# PIN2DMD_Nucleo144.net
KiCad netlist of a schematic drawn in EAGLE
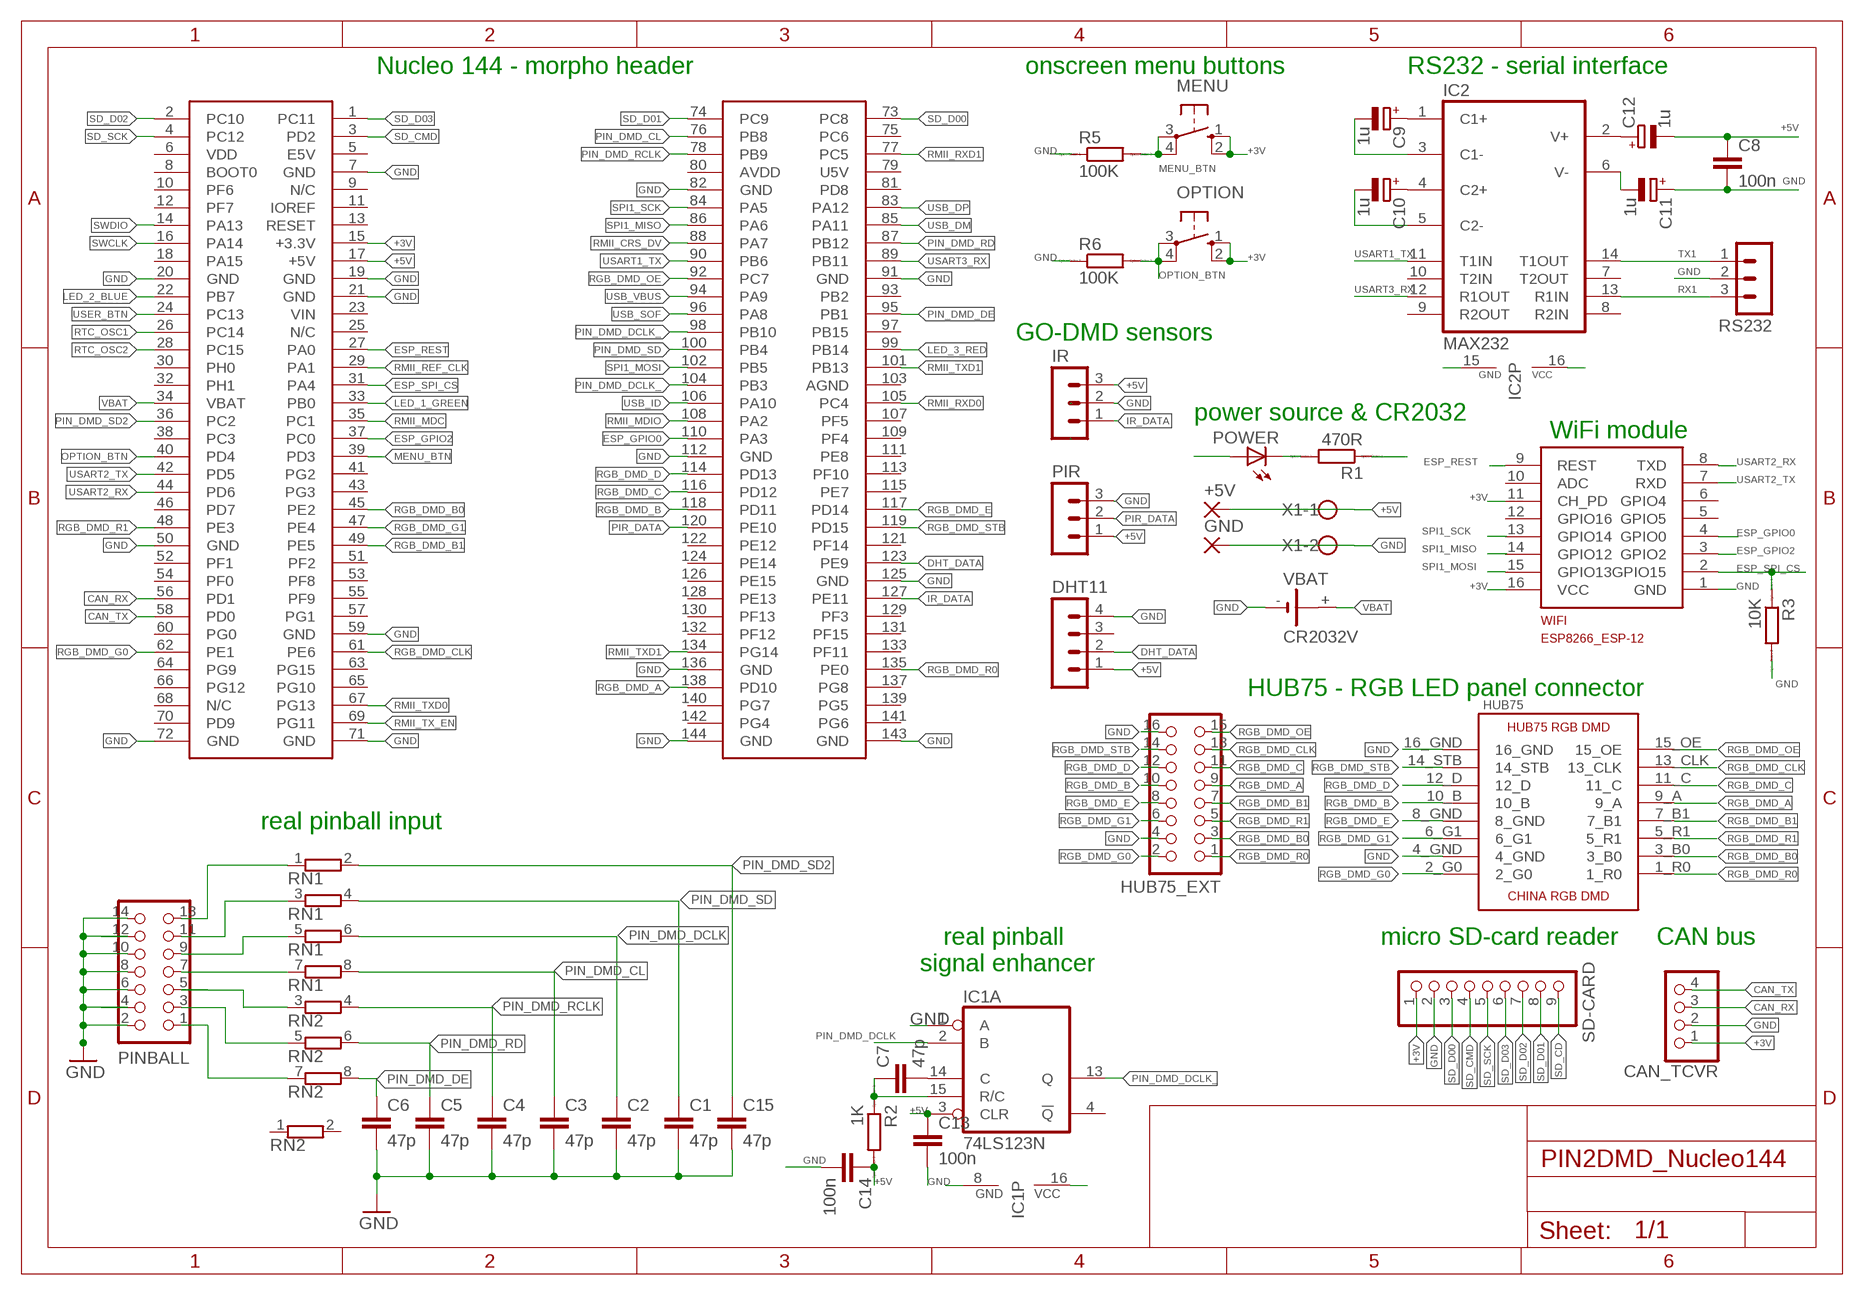
[diagram p0: schematic, sheet 1]

(export (version "E")
  (design (tool "Eeschema 10.0.6"))
  (components
    (comp (ref "+5V")
      (value "WIREPADSMD2,54-5,08")
      (footprint "eagle-import:SMD2,54-5,08")
      (libsource (lib "eagle-import") (part "WIREPADSMD2,54-5,08"))
    )
    (comp (ref "C1")
      (value "47p")
      (footprint "eagle-import:C025-024X044")
      (libsource (lib "eagle-import") (part "C-EU025-024X044"))
    )
    (comp (ref "C2")
      (value "47p")
      (footprint "eagle-import:C025-024X044")
      (libsource (lib "eagle-import") (part "C-EU025-024X044"))
    )
    (comp (ref "C3")
      (value "47p")
      (footprint "eagle-import:C025-024X044")
      (libsource (lib "eagle-import") (part "C-EU025-024X044"))
    )
    (comp (ref "C4")
      (value "47p")
      (footprint "eagle-import:C025-024X044")
      (libsource (lib "eagle-import") (part "C-EU025-024X044"))
    )
    (comp (ref "C5")
      (value "47p")
      (footprint "eagle-import:C025-024X044")
      (libsource (lib "eagle-import") (part "C-EU025-024X044"))
    )
    (comp (ref "C6")
      (value "47p")
      (footprint "eagle-import:C025-024X044")
      (libsource (lib "eagle-import") (part "C-EU025-024X044"))
    )
    (comp (ref "C7")
      (value "47p")
      (footprint "eagle-import:C025-024X044")
      (libsource (lib "eagle-import") (part "C-EU025-024X044"))
    )
    (comp (ref "C8")
      (value "100n")
      (footprint "eagle-import:C025-024X044")
      (libsource (lib "eagle-import") (part "C-EU025-024X044"))
    )
    (comp (ref "C9")
      (value "1u")
      (footprint "eagle-import:E2-4")
      (libsource (lib "eagle-import") (part "CPOL-EUE2-4"))
    )
    (comp (ref "C10")
      (value "1u")
      (footprint "eagle-import:E2-4")
      (libsource (lib "eagle-import") (part "CPOL-EUE2-4"))
    )
    (comp (ref "C11")
      (value "1u")
      (footprint "eagle-import:E2-4")
      (libsource (lib "eagle-import") (part "CPOL-EUE2-4"))
    )
    (comp (ref "C12")
      (value "1u")
      (footprint "eagle-import:E2-4")
      (libsource (lib "eagle-import") (part "CPOL-EUE2-4"))
    )
    (comp (ref "C13")
      (value "100n")
      (footprint "eagle-import:C025-024X044")
      (libsource (lib "eagle-import") (part "C-EU025-024X044"))
    )
    (comp (ref "C14")
      (value "100n")
      (footprint "eagle-import:C025-024X044")
      (libsource (lib "eagle-import") (part "C-EU025-024X044"))
    )
    (comp (ref "C15")
      (value "47p")
      (footprint "eagle-import:C025-024X044")
      (libsource (lib "eagle-import") (part "C-EU025-024X044"))
    )
    (comp (ref "CAN_TCVR")
      (value "PINHD-1X4")
      (footprint "eagle-import:1X04")
      (libsource (lib "eagle-import") (part "PINHD-1X4"))
    )
    (comp (ref "DHT11")
      (value "MA04-1")
      (footprint "eagle-import:MA04-1")
      (libsource (lib "eagle-import") (part "MA04-1"))
    )
    (comp (ref "GND")
      (value "WIREPADSMD2,54-5,08")
      (footprint "eagle-import:SMD2,54-5,08")
      (libsource (lib "eagle-import") (part "WIREPADSMD2,54-5,08"))
    )
    (comp (ref "HUB75")
      (value "RGB_DMD_HUB75_HEADER_FEMALE")
      (footprint "eagle-import:16_PIN_HUB75_RGB_FEMALE_DOWN")
      (libsource (lib "eagle-import") (part "RGB_DMD_HUB75_HEADER_FEMALE"))
    )
    (comp (ref "HUB75_EXT")
      (value "CON_HEADER_2X08B")
      (footprint "eagle-import:PINSHRD_PTH_2X08")
      (libsource (lib "eagle-import") (part "CON_HEADER_2X08B"))
    )
    (comp (ref "IC1")
      (value "74LS123N")
      (footprint "eagle-import:DIL16")
      (libsource (lib "eagle-import") (part "74123NLS"))
    )
    (comp (ref "IC2")
      (value "MAX232")
      (footprint "eagle-import:DIL16")
      (fields (field (name "MF") "MAXIM") (field (name "MPN") "MAX232ACPE+"))
      (libsource (lib "eagle-import") (part "MAX232"))
    )
    (comp (ref "IR")
      (value "MA03-1")
      (footprint "eagle-import:MA03-1")
      (libsource (lib "eagle-import") (part "MA03-1"))
    )
    (comp (ref "MENU")
      (value "10-XX")
      (footprint "eagle-import:B3F-10XX")
      (fields (field (name "MPN") "B3F-1000"))
      (libsource (lib "eagle-import") (part "10-XX"))
    )
    (comp (ref "OPTION")
      (value "10-XX")
      (footprint "eagle-import:B3F-10XX")
      (fields (field (name "MPN") "B3F-1000"))
      (libsource (lib "eagle-import") (part "10-XX"))
    )
    (comp (ref "PINBALL")
      (value "CON_HEADER_2X07-PTH-SHROUDED")
      (footprint "eagle-import:PINSHRD_PTH_2X07")
      (libsource (lib "eagle-import") (part "CON_HEADER_2X07-PTH-SHROUDED"))
    )
    (comp (ref "PIR")
      (value "MA03-1")
      (footprint "eagle-import:MA03-1")
      (libsource (lib "eagle-import") (part "MA03-1"))
    )
    (comp (ref "POWER")
      (value "LED3MM")
      (footprint "eagle-import:LED3MM")
      (libsource (lib "eagle-import") (part "LED3MM"))
    )
    (comp (ref "R1")
      (value "470R")
      (footprint "eagle-import:0207_10")
      (libsource (lib "eagle-import") (part "R0207/10"))
    )
    (comp (ref "R2")
      (value "1K")
      (footprint "eagle-import:0207_10")
      (libsource (lib "eagle-import") (part "R0207/10"))
    )
    (comp (ref "R3")
      (value "10K")
      (footprint "eagle-import:0207_10")
      (libsource (lib "eagle-import") (part "R0207/10"))
    )
    (comp (ref "R5")
      (value "100K")
      (footprint "eagle-import:0207_10")
      (libsource (lib "eagle-import") (part "R0207/10"))
    )
    (comp (ref "R6")
      (value "100K")
      (footprint "eagle-import:0207_10")
      (libsource (lib "eagle-import") (part "R0207/10"))
    )
    (comp (ref "RN1")
      (value "E4RP")
      (footprint "eagle-import:SIL8")
      (libsource (lib "eagle-import") (part "E4RP"))
    )
    (comp (ref "RN2")
      (value "E4RP")
      (footprint "eagle-import:SIL8")
      (libsource (lib "eagle-import") (part "E4RP"))
    )
    (comp (ref "RS232")
      (value "MA03-1")
      (footprint "eagle-import:MA03-1")
      (libsource (lib "eagle-import") (part "MA03-1"))
    )
    (comp (ref "SD-CARD")
      (value "PINHD-1X9")
      (footprint "eagle-import:1X09")
      (libsource (lib "eagle-import") (part "PINHD-1X9"))
    )
    (comp (ref "U$1")
      (value "NUCLEO-144")
      (footprint "eagle-import:NUCLEO-144")
      (libsource (lib "eagle-import") (part "NUCLEO-144"))
    )
    (comp (ref "VBAT")
      (value "CR2032V")
      (footprint "eagle-import:CR2032V")
      (libsource (lib "eagle-import") (part "CR2032V"))
    )
    (comp (ref "WIFI")
      (value "ESP8266_ESP-12")
      (footprint "eagle-import:ESP8266-ESP12")
      (libsource (lib "eagle-import") (part "ESP8266_ESP-12"))
    )
    (comp (ref "X1")
      (value "W237-102")
      (footprint "eagle-import:W237-102")
      (fields (field (name "MPN") "237-102"))
      (libsource (lib "eagle-import") (part "W237-102"))
    )
  )
  (nets
    (net (code "1") (name "+3V") (class "Default")
      (node (ref "CAN_TCVR") (pin "1") (pinfunction "1_1") (pintype "passive"))
      (node (ref "MENU") (pin "1") (pinfunction "S_1") (pintype "passive"))
      (node (ref "MENU") (pin "2") (pinfunction "S1_2") (pintype "passive"))
      (node (ref "OPTION") (pin "1") (pinfunction "S_1") (pintype "passive"))
      (node (ref "OPTION") (pin "2") (pinfunction "S1_2") (pintype "passive"))
      (node (ref "SD-CARD") (pin "1") (pinfunction "1_1") (pintype "passive"))
      (node (ref "U$1") (pin "15") (pinfunction "+3.3V_15") (pintype "bidirectional"))
      (node (ref "WIFI") (pin "11") (pinfunction "CH_PD_11") (pintype "bidirectional"))
      (node (ref "WIFI") (pin "16") (pinfunction "VCC_16") (pintype "bidirectional"))
    )
    (net (code "2") (name "+5V") (class "Default")
      (node (ref "+5V") (pin "1") (pinfunction "P_1") (pintype "passive"))
      (node (ref "C12") (pin "-") (pinfunction "-_-") (pintype "passive"))
      (node (ref "C13") (pin "1") (pinfunction "1_1") (pintype "passive"))
      (node (ref "C14") (pin "1") (pinfunction "1_1") (pintype "passive"))
      (node (ref "C8") (pin "1") (pinfunction "1_1") (pintype "passive"))
      (node (ref "DHT11") (pin "1") (pinfunction "1_1") (pintype "passive"))
      (node (ref "IC1") (pin "16") (pinfunction "VCC_16") (pintype "power_in"))
      (node (ref "IC1") (pin "3") (pinfunction "CLR_3") (pintype "input"))
      (node (ref "IC2") (pin "16") (pinfunction "VCC_16") (pintype "power_in"))
      (node (ref "IR") (pin "3") (pinfunction "3_3") (pintype "passive"))
      (node (ref "PIR") (pin "1") (pinfunction "1_1") (pintype "passive"))
      (node (ref "POWER") (pin "A") (pinfunction "A_A") (pintype "passive"))
      (node (ref "R2") (pin "2") (pinfunction "2_2") (pintype "passive"))
      (node (ref "U$1") (pin "17") (pinfunction "+5V_17") (pintype "bidirectional"))
      (node (ref "X1") (pin "1") (pinfunction "KL_1") (pintype "passive"))
    )
    (net (code "3") (name "/RX1") (class "Default")
      (node (ref "IC2") (pin "13") (pinfunction "R1IN_13") (pintype "input"))
      (node (ref "RS232") (pin "3") (pinfunction "3_3") (pintype "passive"))
    )
    (net (code "4") (name "/TX1") (class "Default")
      (node (ref "IC2") (pin "14") (pinfunction "T1OUT_14") (pintype "output"))
      (node (ref "RS232") (pin "1") (pinfunction "1_1") (pintype "passive"))
    )
    (net (code "5") (name "CAN_RX") (class "Default")
      (node (ref "CAN_TCVR") (pin "3") (pinfunction "3_3") (pintype "passive"))
      (node (ref "U$1") (pin "56") (pinfunction "PD1_56") (pintype "bidirectional"))
    )
    (net (code "6") (name "CAN_TX") (class "Default")
      (node (ref "CAN_TCVR") (pin "4") (pinfunction "4_4") (pintype "passive"))
      (node (ref "U$1") (pin "58") (pinfunction "PD0_58") (pintype "bidirectional"))
    )
    (net (code "7") (name "DHT_DATA") (class "Default")
      (node (ref "DHT11") (pin "2") (pinfunction "2_2") (pintype "passive"))
      (node (ref "U$1") (pin "123") (pinfunction "PE9_123") (pintype "bidirectional"))
    )
    (net (code "8") (name "ESP_GPIO0") (class "Default")
      (node (ref "U$1") (pin "110") (pinfunction "PA3_110") (pintype "bidirectional"))
      (node (ref "WIFI") (pin "4") (pinfunction "GPIO0_4") (pintype "bidirectional"))
    )
    (net (code "9") (name "ESP_GPIO2") (class "Default")
      (node (ref "U$1") (pin "37") (pinfunction "PC0_37") (pintype "bidirectional"))
      (node (ref "WIFI") (pin "3") (pinfunction "GPIO2_3") (pintype "bidirectional"))
    )
    (net (code "10") (name "ESP_REST") (class "Default")
      (node (ref "U$1") (pin "27") (pinfunction "PA0_27") (pintype "bidirectional"))
      (node (ref "WIFI") (pin "9") (pinfunction "REST_9") (pintype "bidirectional"))
    )
    (net (code "11") (name "ESP_SPI_CS") (class "Default")
      (node (ref "R3") (pin "1") (pinfunction "1_1") (pintype "passive"))
      (node (ref "U$1") (pin "31") (pinfunction "PA4_31") (pintype "bidirectional"))
      (node (ref "WIFI") (pin "2") (pinfunction "GPIO15_2") (pintype "bidirectional"))
    )
    (net (code "12") (name "GND") (class "Default")
      (node (ref "C1") (pin "2") (pinfunction "2_2") (pintype "passive"))
      (node (ref "C11") (pin "+") (pinfunction "+_+") (pintype "passive"))
      (node (ref "C13") (pin "2") (pinfunction "2_2") (pintype "passive"))
      (node (ref "C14") (pin "2") (pinfunction "2_2") (pintype "passive"))
      (node (ref "C15") (pin "2") (pinfunction "2_2") (pintype "passive"))
      (node (ref "C2") (pin "2") (pinfunction "2_2") (pintype "passive"))
      (node (ref "C3") (pin "2") (pinfunction "2_2") (pintype "passive"))
      (node (ref "C4") (pin "2") (pinfunction "2_2") (pintype "passive"))
      (node (ref "C5") (pin "2") (pinfunction "2_2") (pintype "passive"))
      (node (ref "C6") (pin "2") (pinfunction "2_2") (pintype "passive"))
      (node (ref "C8") (pin "2") (pinfunction "2_2") (pintype "passive"))
      (node (ref "CAN_TCVR") (pin "2") (pinfunction "2_2") (pintype "passive"))
      (node (ref "DHT11") (pin "4") (pinfunction "4_4") (pintype "passive"))
      (node (ref "GND") (pin "1") (pinfunction "P_1") (pintype "passive"))
      (node (ref "HUB75") (pin "16_GND") (pinfunction "16_GND_16_GND") (pintype "bidirectional"))
      (node (ref "HUB75") (pin "4_GND") (pinfunction "4_GND_4_GND") (pintype "bidirectional"))
      (node (ref "HUB75_EXT") (pin "16") (pinfunction "16_16") (pintype "passive"))
      (node (ref "HUB75_EXT") (pin "4") (pinfunction "4_4") (pintype "passive"))
      (node (ref "IC1") (pin "1") (pinfunction "A_1") (pintype "input"))
      (node (ref "IC1") (pin "8") (pinfunction "GND_8") (pintype "power_in"))
      (node (ref "IC2") (pin "15") (pinfunction "GND_15") (pintype "power_in"))
      (node (ref "IR") (pin "2") (pinfunction "2_2") (pintype "passive"))
      (node (ref "PINBALL") (pin "10") (pinfunction "10_10") (pintype "passive"))
      (node (ref "PINBALL") (pin "12") (pinfunction "12_12") (pintype "passive"))
      (node (ref "PINBALL") (pin "14") (pinfunction "14_14") (pintype "passive"))
      (node (ref "PINBALL") (pin "2") (pinfunction "2_2") (pintype "passive"))
      (node (ref "PINBALL") (pin "4") (pinfunction "4_4") (pintype "passive"))
      (node (ref "PINBALL") (pin "6") (pinfunction "6_6") (pintype "passive"))
      (node (ref "PINBALL") (pin "8") (pinfunction "8_8") (pintype "passive"))
      (node (ref "PIR") (pin "3") (pinfunction "3_3") (pintype "passive"))
      (node (ref "R1") (pin "1") (pinfunction "1_1") (pintype "passive"))
      (node (ref "R3") (pin "2") (pinfunction "2_2") (pintype "passive"))
      (node (ref "R5") (pin "1") (pinfunction "1_1") (pintype "passive"))
      (node (ref "R6") (pin "1") (pinfunction "1_1") (pintype "passive"))
      (node (ref "RS232") (pin "2") (pinfunction "2_2") (pintype "passive"))
      (node (ref "SD-CARD") (pin "2") (pinfunction "2_2") (pintype "passive"))
      (node (ref "U$1") (pin "112") (pinfunction "GND_112") (pintype "bidirectional"))
      (node (ref "U$1") (pin "125") (pinfunction "GND_125") (pintype "bidirectional"))
      (node (ref "U$1") (pin "136") (pinfunction "GND_136") (pintype "bidirectional"))
      (node (ref "U$1") (pin "143") (pinfunction "GND_143") (pintype "bidirectional"))
      (node (ref "U$1") (pin "144") (pinfunction "GND_144") (pintype "bidirectional"))
      (node (ref "U$1") (pin "19") (pinfunction "GND_19") (pintype "bidirectional"))
      (node (ref "U$1") (pin "20") (pinfunction "GND_20") (pintype "bidirectional"))
      (node (ref "U$1") (pin "21") (pinfunction "GND_21") (pintype "bidirectional"))
      (node (ref "U$1") (pin "50") (pinfunction "GND_50") (pintype "bidirectional"))
      (node (ref "U$1") (pin "59") (pinfunction "GND_59") (pintype "bidirectional"))
      (node (ref "U$1") (pin "7") (pinfunction "GND_7") (pintype "bidirectional"))
      (node (ref "U$1") (pin "71") (pinfunction "GND_71") (pintype "bidirectional"))
      (node (ref "U$1") (pin "72") (pinfunction "GND_72") (pintype "bidirectional"))
      (node (ref "U$1") (pin "82") (pinfunction "GND_82") (pintype "bidirectional"))
      (node (ref "U$1") (pin "91") (pinfunction "GND_91") (pintype "bidirectional"))
      (node (ref "VBAT") (pin "-") (pinfunction "-_-") (pintype "passive"))
      (node (ref "WIFI") (pin "1") (pinfunction "GND_1") (pintype "bidirectional"))
      (node (ref "X1") (pin "2") (pinfunction "KL_2") (pintype "passive"))
    )
    (net (code "13") (name "IR_DATA") (class "Default")
      (node (ref "IR") (pin "1") (pinfunction "1_1") (pintype "passive"))
      (node (ref "U$1") (pin "127") (pinfunction "PE11_127") (pintype "bidirectional"))
    )
    (net (code "14") (name "LED_1_GREEN") (class "Default")
      (node (ref "U$1") (pin "33") (pinfunction "PB0_33") (pintype "bidirectional"))
    )
    (net (code "15") (name "LED_2_BLUE") (class "Default")
      (node (ref "U$1") (pin "22") (pinfunction "PB7_22") (pintype "bidirectional"))
    )
    (net (code "16") (name "LED_3_RED") (class "Default")
      (node (ref "U$1") (pin "99") (pinfunction "PB14_99") (pintype "bidirectional"))
    )
    (net (code "17") (name "MENU_BTN") (class "Default")
      (node (ref "MENU") (pin "3") (pinfunction "P_3") (pintype "passive"))
      (node (ref "MENU") (pin "4") (pinfunction "P1_4") (pintype "passive"))
      (node (ref "R5") (pin "2") (pinfunction "2_2") (pintype "passive"))
      (node (ref "U$1") (pin "39") (pinfunction "PD3_39") (pintype "bidirectional"))
    )
    (net (code "18") (name "Net-(IC1A-C)") (class "Default")
      (node (ref "C7") (pin "2") (pinfunction "2_2") (pintype "passive"))
      (node (ref "IC1") (pin "14") (pinfunction "C_14") (pintype "input"))
    )
    (net (code "19") (name "Net-(IC1A-R{slash}C)") (class "Default")
      (node (ref "C7") (pin "1") (pinfunction "1_1") (pintype "passive"))
      (node (ref "IC1") (pin "15") (pinfunction "R/C_15") (pintype "input"))
      (node (ref "R2") (pin "1") (pinfunction "1_1") (pintype "passive"))
    )
    (net (code "20") (name "Net-(IC2A-C1+)") (class "Default")
      (node (ref "C9") (pin "+") (pinfunction "+_+") (pintype "passive"))
      (node (ref "IC2") (pin "1") (pinfunction "C1+_1") (pintype "bidirectional"))
    )
    (net (code "21") (name "Net-(IC2A-C1-)") (class "Default")
      (node (ref "C9") (pin "-") (pinfunction "-_-") (pintype "passive"))
      (node (ref "IC2") (pin "3") (pinfunction "C1-_3") (pintype "bidirectional"))
    )
    (net (code "22") (name "Net-(IC2A-C2+)") (class "Default")
      (node (ref "C10") (pin "+") (pinfunction "+_+") (pintype "passive"))
      (node (ref "IC2") (pin "4") (pinfunction "C2+_4") (pintype "bidirectional"))
    )
    (net (code "23") (name "Net-(IC2A-C2-)") (class "Default")
      (node (ref "C10") (pin "-") (pinfunction "-_-") (pintype "passive"))
      (node (ref "IC2") (pin "5") (pinfunction "C2-_5") (pintype "bidirectional"))
    )
    (net (code "24") (name "Net-(IC2A-V+)") (class "Default")
      (node (ref "C12") (pin "+") (pinfunction "+_+") (pintype "passive"))
      (node (ref "IC2") (pin "2") (pinfunction "V+_2") (pintype "bidirectional"))
    )
    (net (code "25") (name "Net-(IC2A-V-)") (class "Default")
      (node (ref "C11") (pin "-") (pinfunction "-_-") (pintype "passive"))
      (node (ref "IC2") (pin "6") (pinfunction "V-_6") (pintype "bidirectional"))
    )
    (net (code "26") (name "Net-(PINBALL-Pad13)") (class "Default")
      (node (ref "PINBALL") (pin "13") (pinfunction "13_13") (pintype "passive"))
      (node (ref "RN1") (pin "1") (pinfunction "1_1") (pintype "passive"))
    )
    (net (code "27") (name "Net-(POWER-C)") (class "Default")
      (node (ref "POWER") (pin "K") (pinfunction "C_K") (pintype "passive"))
      (node (ref "R1") (pin "2") (pinfunction "2_2") (pintype "passive"))
    )
    (net (code "28") (name "Net-(RN1B-1)") (class "Default")
      (node (ref "PINBALL") (pin "11") (pinfunction "11_11") (pintype "passive"))
      (node (ref "RN1") (pin "3") (pinfunction "1_3") (pintype "passive"))
    )
    (net (code "29") (name "Net-(RN1C-1)") (class "Default")
      (node (ref "PINBALL") (pin "9") (pinfunction "9_9") (pintype "passive"))
      (node (ref "RN1") (pin "5") (pinfunction "1_5") (pintype "passive"))
    )
    (net (code "30") (name "Net-(RN1D-1)") (class "Default")
      (node (ref "PINBALL") (pin "7") (pinfunction "7_7") (pintype "passive"))
      (node (ref "RN1") (pin "7") (pinfunction "1_7") (pintype "passive"))
    )
    (net (code "31") (name "Net-(RN2B-1)") (class "Default")
      (node (ref "PINBALL") (pin "5") (pinfunction "5_5") (pintype "passive"))
      (node (ref "RN2") (pin "3") (pinfunction "1_3") (pintype "passive"))
    )
    (net (code "32") (name "Net-(RN2C-1)") (class "Default")
      (node (ref "PINBALL") (pin "3") (pinfunction "3_3") (pintype "passive"))
      (node (ref "RN2") (pin "5") (pinfunction "1_5") (pintype "passive"))
    )
    (net (code "33") (name "Net-(RN2D-1)") (class "Default")
      (node (ref "PINBALL") (pin "1") (pinfunction "1_1") (pintype "passive"))
      (node (ref "RN2") (pin "7") (pinfunction "1_7") (pintype "passive"))
    )
    (net (code "34") (name "OPTION_BTN") (class "Default")
      (node (ref "OPTION") (pin "3") (pinfunction "P_3") (pintype "passive"))
      (node (ref "OPTION") (pin "4") (pinfunction "P1_4") (pintype "passive"))
      (node (ref "R6") (pin "2") (pinfunction "2_2") (pintype "passive"))
      (node (ref "U$1") (pin "40") (pinfunction "PD4_40") (pintype "bidirectional"))
    )
    (net (code "35") (name "PIN_DMD_CL") (class "Default")
      (node (ref "C3") (pin "1") (pinfunction "1_1") (pintype "passive"))
      (node (ref "RN1") (pin "8") (pinfunction "2_8") (pintype "passive"))
      (node (ref "U$1") (pin "76") (pinfunction "PB8_76") (pintype "bidirectional"))
    )
    (net (code "36") (name "PIN_DMD_DCLK") (class "Default")
      (node (ref "C2") (pin "1") (pinfunction "1_1") (pintype "passive"))
      (node (ref "IC1") (pin "2") (pinfunction "B_2") (pintype "input"))
      (node (ref "RN1") (pin "6") (pinfunction "2_6") (pintype "passive"))
    )
    (net (code "37") (name "PIN_DMD_DCLK_") (class "Default")
      (node (ref "IC1") (pin "13") (pinfunction "Q_13") (pintype "output"))
      (node (ref "U$1") (pin "104") (pinfunction "PB3_104") (pintype "bidirectional"))
      (node (ref "U$1") (pin "98") (pinfunction "PB10_98") (pintype "bidirectional"))
    )
    (net (code "38") (name "PIN_DMD_DE") (class "Default")
      (node (ref "C6") (pin "1") (pinfunction "1_1") (pintype "passive"))
      (node (ref "RN2") (pin "8") (pinfunction "2_8") (pintype "passive"))
      (node (ref "U$1") (pin "95") (pinfunction "PB1_95") (pintype "bidirectional"))
    )
    (net (code "39") (name "PIN_DMD_RCLK") (class "Default")
      (node (ref "C4") (pin "1") (pinfunction "1_1") (pintype "passive"))
      (node (ref "RN2") (pin "4") (pinfunction "2_4") (pintype "passive"))
      (node (ref "U$1") (pin "78") (pinfunction "PB9_78") (pintype "bidirectional"))
    )
    (net (code "40") (name "PIN_DMD_RD") (class "Default")
      (node (ref "C5") (pin "1") (pinfunction "1_1") (pintype "passive"))
      (node (ref "RN2") (pin "6") (pinfunction "2_6") (pintype "passive"))
      (node (ref "U$1") (pin "87") (pinfunction "PB12_87") (pintype "bidirectional"))
    )
    (net (code "41") (name "PIN_DMD_SD") (class "Default")
      (node (ref "C1") (pin "1") (pinfunction "1_1") (pintype "passive"))
      (node (ref "RN1") (pin "4") (pinfunction "2_4") (pintype "passive"))
      (node (ref "U$1") (pin "100") (pinfunction "PB4_100") (pintype "bidirectional"))
    )
    (net (code "42") (name "PIN_DMD_SD2") (class "Default")
      (node (ref "C15") (pin "1") (pinfunction "1_1") (pintype "passive"))
      (node (ref "RN1") (pin "2") (pinfunction "2_2") (pintype "passive"))
      (node (ref "U$1") (pin "36") (pinfunction "PC2_36") (pintype "bidirectional"))
    )
    (net (code "43") (name "PIR_DATA") (class "Default")
      (node (ref "PIR") (pin "2") (pinfunction "2_2") (pintype "passive"))
      (node (ref "U$1") (pin "120") (pinfunction "PE10_120") (pintype "bidirectional"))
    )
    (net (code "44") (name "RGB_DMD_A") (class "Default")
      (node (ref "HUB75") (pin "9_A") (pinfunction "9_A_9_A") (pintype "bidirectional"))
      (node (ref "HUB75_EXT") (pin "9") (pinfunction "9_9") (pintype "passive"))
      (node (ref "U$1") (pin "138") (pinfunction "PD10_138") (pintype "bidirectional"))
    )
    (net (code "45") (name "RGB_DMD_B") (class "Default")
      (node (ref "HUB75") (pin "10_B") (pinfunction "10_B_10_B") (pintype "bidirectional"))
      (node (ref "HUB75_EXT") (pin "10") (pinfunction "10_10") (pintype "passive"))
      (node (ref "U$1") (pin "118") (pinfunction "PD11_118") (pintype "bidirectional"))
    )
    (net (code "46") (name "RGB_DMD_B0") (class "Default")
      (node (ref "HUB75") (pin "3_B0") (pinfunction "3_B0_3_B0") (pintype "bidirectional"))
      (node (ref "HUB75_EXT") (pin "3") (pinfunction "3_3") (pintype "passive"))
      (node (ref "U$1") (pin "45") (pinfunction "PE2_45") (pintype "bidirectional"))
    )
    (net (code "47") (name "RGB_DMD_B1") (class "Default")
      (node (ref "HUB75") (pin "7_B1") (pinfunction "7_B1_7_B1") (pintype "bidirectional"))
      (node (ref "HUB75_EXT") (pin "7") (pinfunction "7_7") (pintype "passive"))
      (node (ref "U$1") (pin "49") (pinfunction "PE5_49") (pintype "bidirectional"))
    )
    (net (code "48") (name "RGB_DMD_C") (class "Default")
      (node (ref "HUB75") (pin "11_C") (pinfunction "11_C_11_C") (pintype "bidirectional"))
      (node (ref "HUB75_EXT") (pin "11") (pinfunction "11_11") (pintype "passive"))
      (node (ref "U$1") (pin "116") (pinfunction "PD12_116") (pintype "bidirectional"))
    )
    (net (code "49") (name "RGB_DMD_CLK") (class "Default")
      (node (ref "HUB75") (pin "13_CLK") (pinfunction "13_CLK_13_CLK") (pintype "bidirectional"))
      (node (ref "HUB75_EXT") (pin "13") (pinfunction "13_13") (pintype "passive"))
      (node (ref "U$1") (pin "61") (pinfunction "PE6_61") (pintype "bidirectional"))
    )
    (net (code "50") (name "RGB_DMD_D") (class "Default")
      (node (ref "HUB75") (pin "12_D") (pinfunction "12_D_12_D") (pintype "bidirectional"))
      (node (ref "HUB75_EXT") (pin "12") (pinfunction "12_12") (pintype "passive"))
      (node (ref "U$1") (pin "114") (pinfunction "PD13_114") (pintype "bidirectional"))
    )
    (net (code "51") (name "RGB_DMD_E") (class "Default")
      (node (ref "HUB75") (pin "8_GND") (pinfunction "8_GND_8_GND") (pintype "bidirectional"))
      (node (ref "HUB75_EXT") (pin "8") (pinfunction "8_8") (pintype "passive"))
      (node (ref "U$1") (pin "117") (pinfunction "PD14_117") (pintype "bidirectional"))
    )
    (net (code "52") (name "RGB_DMD_G0") (class "Default")
      (node (ref "HUB75") (pin "2_G0") (pinfunction "2_G0_2_G0") (pintype "bidirectional"))
      (node (ref "HUB75_EXT") (pin "2") (pinfunction "2_2") (pintype "passive"))
      (node (ref "U$1") (pin "62") (pinfunction "PE1_62") (pintype "bidirectional"))
    )
    (net (code "53") (name "RGB_DMD_G1") (class "Default")
      (node (ref "HUB75") (pin "6_G1") (pinfunction "6_G1_6_G1") (pintype "bidirectional"))
      (node (ref "HUB75_EXT") (pin "6") (pinfunction "6_6") (pintype "passive"))
      (node (ref "U$1") (pin "47") (pinfunction "PE4_47") (pintype "bidirectional"))
    )
    (net (code "54") (name "RGB_DMD_OE") (class "Default")
      (node (ref "HUB75") (pin "15_OE") (pinfunction "15_OE_15_OE") (pintype "bidirectional"))
      (node (ref "HUB75_EXT") (pin "15") (pinfunction "15_15") (pintype "passive"))
      (node (ref "U$1") (pin "92") (pinfunction "PC7_92") (pintype "bidirectional"))
    )
    (net (code "55") (name "RGB_DMD_R0") (class "Default")
      (node (ref "HUB75") (pin "1_R0") (pinfunction "1_R0_1_R0") (pintype "bidirectional"))
      (node (ref "HUB75_EXT") (pin "1") (pinfunction "1_1") (pintype "passive"))
      (node (ref "U$1") (pin "135") (pinfunction "PE0_135") (pintype "bidirectional"))
    )
    (net (code "56") (name "RGB_DMD_R1") (class "Default")
      (node (ref "HUB75") (pin "5_R1") (pinfunction "5_R1_5_R1") (pintype "bidirectional"))
      (node (ref "HUB75_EXT") (pin "5") (pinfunction "5_5") (pintype "passive"))
      (node (ref "U$1") (pin "48") (pinfunction "PE3_48") (pintype "bidirectional"))
    )
    (net (code "57") (name "RGB_DMD_STB") (class "Default")
      (node (ref "HUB75") (pin "14_STB") (pinfunction "14_STB_14_STB") (pintype "bidirectional"))
      (node (ref "HUB75_EXT") (pin "14") (pinfunction "14_14") (pintype "passive"))
      (node (ref "U$1") (pin "119") (pinfunction "PD15_119") (pintype "bidirectional"))
    )
    (net (code "58") (name "RMII_CRS_DV") (class "Default")
      (node (ref "U$1") (pin "88") (pinfunction "PA7_88") (pintype "bidirectional"))
    )
    (net (code "59") (name "RMII_MDC") (class "Default")
      (node (ref "U$1") (pin "35") (pinfunction "PC1_35") (pintype "bidirectional"))
    )
    (net (code "60") (name "RMII_MDIO") (class "Default")
      (node (ref "U$1") (pin "108") (pinfunction "PA2_108") (pintype "bidirectional"))
    )
    (net (code "61") (name "RMII_REF_CLK") (class "Default")
      (node (ref "U$1") (pin "29") (pinfunction "PA1_29") (pintype "bidirectional"))
    )
    (net (code "62") (name "RMII_RXD0") (class "Default")
      (node (ref "U$1") (pin "105") (pinfunction "PC4_105") (pintype "bidirectional"))
    )
    (net (code "63") (name "RMII_RXD1") (class "Default")
      (node (ref "U$1") (pin "77") (pinfunction "PC5_77") (pintype "bidirectional"))
    )
    (net (code "64") (name "RMII_TXD0") (class "Default")
      (node (ref "U$1") (pin "67") (pinfunction "PG13_67") (pintype "bidirectional"))
    )
    (net (code "65") (name "RMII_TXD1") (class "Default")
      (node (ref "U$1") (pin "101") (pinfunction "PB13_101") (pintype "bidirectional"))
      (node (ref "U$1") (pin "134") (pinfunction "PG14_134") (pintype "bidirectional"))
    )
    (net (code "66") (name "RMII_TX_EN") (class "Default")
      (node (ref "U$1") (pin "69") (pinfunction "PG11_69") (pintype "bidirectional"))
    )
    (net (code "67") (name "RTC_OSC1") (class "Default")
      (node (ref "U$1") (pin "26") (pinfunction "PC14_26") (pintype "bidirectional"))
    )
    (net (code "68") (name "RTC_OSC2") (class "Default")
      (node (ref "U$1") (pin "28") (pinfunction "PC15_28") (pintype "bidirectional"))
    )
    (net (code "69") (name "SD_CD") (class "Default")
      (node (ref "SD-CARD") (pin "9") (pinfunction "9_9") (pintype "passive"))
    )
    (net (code "70") (name "SD_CMD") (class "Default")
      (node (ref "SD-CARD") (pin "4") (pinfunction "4_4") (pintype "passive"))
      (node (ref "U$1") (pin "3") (pinfunction "PD2_3") (pintype "bidirectional"))
    )
    (net (code "71") (name "SD_D00") (class "Default")
      (node (ref "SD-CARD") (pin "3") (pinfunction "3_3") (pintype "passive"))
      (node (ref "U$1") (pin "73") (pinfunction "PC8_73") (pintype "bidirectional"))
    )
    (net (code "72") (name "SD_D01") (class "Default")
      (node (ref "SD-CARD") (pin "8") (pinfunction "8_8") (pintype "passive"))
      (node (ref "U$1") (pin "74") (pinfunction "PC9_74") (pintype "bidirectional"))
    )
    (net (code "73") (name "SD_D02") (class "Default")
      (node (ref "SD-CARD") (pin "7") (pinfunction "7_7") (pintype "passive"))
      (node (ref "U$1") (pin "2") (pinfunction "PC10_2") (pintype "bidirectional"))
    )
    (net (code "74") (name "SD_D03") (class "Default")
      (node (ref "SD-CARD") (pin "6") (pinfunction "6_6") (pintype "passive"))
      (node (ref "U$1") (pin "1") (pinfunction "PC11_1") (pintype "bidirectional"))
    )
    (net (code "75") (name "SD_SCK") (class "Default")
      (node (ref "SD-CARD") (pin "5") (pinfunction "5_5") (pintype "passive"))
      (node (ref "U$1") (pin "4") (pinfunction "PC12_4") (pintype "bidirectional"))
    )
    (net (code "76") (name "SPI1_MISO") (class "Default")
      (node (ref "U$1") (pin "86") (pinfunction "PA6_86") (pintype "bidirectional"))
      (node (ref "WIFI") (pin "14") (pinfunction "GPIO12_14") (pintype "bidirectional"))
    )
    (net (code "77") (name "SPI1_MOSI") (class "Default")
      (node (ref "U$1") (pin "102") (pinfunction "PB5_102") (pintype "bidirectional"))
      (node (ref "WIFI") (pin "15") (pinfunction "GPIO13_15") (pintype "bidirectional"))
    )
    (net (code "78") (name "SPI1_SCK") (class "Default")
      (node (ref "U$1") (pin "84") (pinfunction "PA5_84") (pintype "bidirectional"))
      (node (ref "WIFI") (pin "13") (pinfunction "GPIO14_13") (pintype "bidirectional"))
    )
    (net (code "79") (name "SWCLK") (class "Default")
      (node (ref "U$1") (pin "16") (pinfunction "PA14_16") (pintype "bidirectional"))
    )
    (net (code "80") (name "SWDIO") (class "Default")
      (node (ref "U$1") (pin "14") (pinfunction "PA13_14") (pintype "bidirectional"))
    )
    (net (code "81") (name "USART1_TX") (class "Default")
      (node (ref "IC2") (pin "11") (pinfunction "T1IN_11") (pintype "input"))
      (node (ref "U$1") (pin "90") (pinfunction "PB6_90") (pintype "bidirectional"))
    )
    (net (code "82") (name "USART2_RX") (class "Default")
      (node (ref "U$1") (pin "44") (pinfunction "PD6_44") (pintype "bidirectional"))
      (node (ref "WIFI") (pin "8") (pinfunction "TXD_8") (pintype "bidirectional"))
    )
    (net (code "83") (name "USART2_TX") (class "Default")
      (node (ref "U$1") (pin "42") (pinfunction "PD5_42") (pintype "bidirectional"))
      (node (ref "WIFI") (pin "7") (pinfunction "RXD_7") (pintype "bidirectional"))
    )
    (net (code "84") (name "USART3_RX") (class "Default")
      (node (ref "IC2") (pin "12") (pinfunction "R1OUT_12") (pintype "output"))
      (node (ref "U$1") (pin "89") (pinfunction "PB11_89") (pintype "bidirectional"))
    )
    (net (code "85") (name "USB_DM") (class "Default")
      (node (ref "U$1") (pin "85") (pinfunction "PA11_85") (pintype "bidirectional"))
    )
    (net (code "86") (name "USB_DP") (class "Default")
      (node (ref "U$1") (pin "83") (pinfunction "PA12_83") (pintype "bidirectional"))
    )
    (net (code "87") (name "USB_ID") (class "Default")
      (node (ref "U$1") (pin "106") (pinfunction "PA10_106") (pintype "bidirectional"))
    )
    (net (code "88") (name "USB_SOF") (class "Default")
      (node (ref "U$1") (pin "96") (pinfunction "PA8_96") (pintype "bidirectional"))
    )
    (net (code "89") (name "USB_VBUS") (class "Default")
      (node (ref "U$1") (pin "94") (pinfunction "PA9_94") (pintype "bidirectional"))
    )
    (net (code "90") (name "USER_BTN") (class "Default")
      (node (ref "U$1") (pin "24") (pinfunction "PC13_24") (pintype "bidirectional"))
    )
    (net (code "91") (name "VBAT") (class "Default")
      (node (ref "U$1") (pin "34") (pinfunction "VBAT_34") (pintype "bidirectional"))
      (node (ref "VBAT") (pin "+") (pinfunction "+_+") (pintype "passive"))
    )
    (net (code "92") (name "unconnected-(DHT11-Pad3)") (class "Default")
      (node (ref "DHT11") (pin "3") (pinfunction "3_3") (pintype "passive"))
    )
    (net (code "93") (name "unconnected-(IC1A-~{Q}-Pad4)") (class "Default")
      (node (ref "IC1") (pin "4") (pinfunction "~{Q}_4") (pintype "output"))
    )
    (net (code "94") (name "unconnected-(IC2A-R2IN-Pad8)") (class "Default")
      (node (ref "IC2") (pin "8") (pinfunction "R2IN_8") (pintype "input"))
    )
    (net (code "95") (name "unconnected-(IC2A-R2OUT-Pad9)") (class "Default")
      (node (ref "IC2") (pin "9") (pinfunction "R2OUT_9") (pintype "output"))
    )
    (net (code "96") (name "unconnected-(IC2A-T2IN-Pad10)") (class "Default")
      (node (ref "IC2") (pin "10") (pinfunction "T2IN_10") (pintype "input"))
    )
    (net (code "97") (name "unconnected-(IC2A-T2OUT-Pad7)") (class "Default")
      (node (ref "IC2") (pin "7") (pinfunction "T2OUT_7") (pintype "output"))
    )
    (net (code "98") (name "unconnected-(RN2-Pad1)") (class "Default")
      (node (ref "RN2") (pin "1") (pinfunction "1_1") (pintype "passive"))
    )
    (net (code "99") (name "unconnected-(RN2-Pad2)") (class "Default")
      (node (ref "RN2") (pin "2") (pinfunction "2_2") (pintype "passive"))
    )
    (net (code "100") (name "unconnected-(U$1-AGND-Pad103)") (class "Default")
      (node (ref "U$1") (pin "103") (pinfunction "AGND_103") (pintype "bidirectional"))
    )
    (net (code "101") (name "unconnected-(U$1-AVDD-Pad80)") (class "Default")
      (node (ref "U$1") (pin "80") (pinfunction "AVDD_80") (pintype "bidirectional"))
    )
    (net (code "102") (name "unconnected-(U$1-BOOT0-Pad8)") (class "Default")
      (node (ref "U$1") (pin "8") (pinfunction "BOOT0_8") (pintype "bidirectional"))
    )
    (net (code "103") (name "unconnected-(U$1-E5V-Pad5)") (class "Default")
      (node (ref "U$1") (pin "5") (pinfunction "E5V_5") (pintype "bidirectional"))
    )
    (net (code "104") (name "unconnected-(U$1-IOREF-Pad11)") (class "Default")
      (node (ref "U$1") (pin "11") (pinfunction "IOREF_11") (pintype "bidirectional"))
    )
    (net (code "105") (name "unconnected-(U$1-N{slash}C-Pad9)") (class "Default")
      (node (ref "U$1") (pin "9") (pinfunction "N/C_9") (pintype "bidirectional"))
    )
    (net (code "106") (name "unconnected-(U$1-N{slash}C-Pad25)") (class "Default")
      (node (ref "U$1") (pin "25") (pinfunction "N/C_25") (pintype "bidirectional"))
    )
    (net (code "107") (name "unconnected-(U$1-N{slash}C-Pad68)") (class "Default")
      (node (ref "U$1") (pin "68") (pinfunction "N/C_68") (pintype "bidirectional"))
    )
    (net (code "108") (name "unconnected-(U$1-PA15-Pad18)") (class "Default")
      (node (ref "U$1") (pin "18") (pinfunction "PA15_18") (pintype "bidirectional"))
    )
    (net (code "109") (name "unconnected-(U$1-PB2-Pad93)") (class "Default")
      (node (ref "U$1") (pin "93") (pinfunction "PB2_93") (pintype "bidirectional"))
    )
    (net (code "110") (name "unconnected-(U$1-PB15-Pad97)") (class "Default")
      (node (ref "U$1") (pin "97") (pinfunction "PB15_97") (pintype "bidirectional"))
    )
    (net (code "111") (name "unconnected-(U$1-PC3-Pad38)") (class "Default")
      (node (ref "U$1") (pin "38") (pinfunction "PC3_38") (pintype "bidirectional"))
    )
    (net (code "112") (name "unconnected-(U$1-PC6-Pad75)") (class "Default")
      (node (ref "U$1") (pin "75") (pinfunction "PC6_75") (pintype "bidirectional"))
    )
    (net (code "113") (name "unconnected-(U$1-PD7-Pad46)") (class "Default")
      (node (ref "U$1") (pin "46") (pinfunction "PD7_46") (pintype "bidirectional"))
    )
    (net (code "114") (name "unconnected-(U$1-PD8-Pad81)") (class "Default")
      (node (ref "U$1") (pin "81") (pinfunction "PD8_81") (pintype "bidirectional"))
    )
    (net (code "115") (name "unconnected-(U$1-PD9-Pad70)") (class "Default")
      (node (ref "U$1") (pin "70") (pinfunction "PD9_70") (pintype "bidirectional"))
    )
    (net (code "116") (name "unconnected-(U$1-PE7-Pad115)") (class "Default")
      (node (ref "U$1") (pin "115") (pinfunction "PE7_115") (pintype "bidirectional"))
    )
    (net (code "117") (name "unconnected-(U$1-PE8-Pad111)") (class "Default")
      (node (ref "U$1") (pin "111") (pinfunction "PE8_111") (pintype "bidirectional"))
    )
    (net (code "118") (name "unconnected-(U$1-PE12-Pad122)") (class "Default")
      (node (ref "U$1") (pin "122") (pinfunction "PE12_122") (pintype "bidirectional"))
    )
    (net (code "119") (name "unconnected-(U$1-PE13-Pad128)") (class "Default")
      (node (ref "U$1") (pin "128") (pinfunction "PE13_128") (pintype "bidirectional"))
    )
    (net (code "120") (name "unconnected-(U$1-PE14-Pad124)") (class "Default")
      (node (ref "U$1") (pin "124") (pinfunction "PE14_124") (pintype "bidirectional"))
    )
    (net (code "121") (name "unconnected-(U$1-PE15-Pad126)") (class "Default")
      (node (ref "U$1") (pin "126") (pinfunction "PE15_126") (pintype "bidirectional"))
    )
    (net (code "122") (name "unconnected-(U$1-PF0-Pad54)") (class "Default")
      (node (ref "U$1") (pin "54") (pinfunction "PF0_54") (pintype "bidirectional"))
    )
    (net (code "123") (name "unconnected-(U$1-PF1-Pad52)") (class "Default")
      (node (ref "U$1") (pin "52") (pinfunction "PF1_52") (pintype "bidirectional"))
    )
    (net (code "124") (name "unconnected-(U$1-PF2-Pad51)") (class "Default")
      (node (ref "U$1") (pin "51") (pinfunction "PF2_51") (pintype "bidirectional"))
    )
    (net (code "125") (name "unconnected-(U$1-PF3-Pad129)") (class "Default")
      (node (ref "U$1") (pin "129") (pinfunction "PF3_129") (pintype "bidirectional"))
    )
    (net (code "126") (name "unconnected-(U$1-PF4-Pad109)") (class "Default")
      (node (ref "U$1") (pin "109") (pinfunction "PF4_109") (pintype "bidirectional"))
    )
    (net (code "127") (name "unconnected-(U$1-PF5-Pad107)") (class "Default")
      (node (ref "U$1") (pin "107") (pinfunction "PF5_107") (pintype "bidirectional"))
    )
    (net (code "128") (name "unconnected-(U$1-PF6-Pad10)") (class "Default")
      (node (ref "U$1") (pin "10") (pinfunction "PF6_10") (pintype "bidirectional"))
    )
    (net (code "129") (name "unconnected-(U$1-PF7-Pad12)") (class "Default")
      (node (ref "U$1") (pin "12") (pinfunction "PF7_12") (pintype "bidirectional"))
    )
    (net (code "130") (name "unconnected-(U$1-PF8-Pad53)") (class "Default")
      (node (ref "U$1") (pin "53") (pinfunction "PF8_53") (pintype "bidirectional"))
    )
    (net (code "131") (name "unconnected-(U$1-PF9-Pad55)") (class "Default")
      (node (ref "U$1") (pin "55") (pinfunction "PF9_55") (pintype "bidirectional"))
    )
    (net (code "132") (name "unconnected-(U$1-PF10-Pad113)") (class "Default")
      (node (ref "U$1") (pin "113") (pinfunction "PF10_113") (pintype "bidirectional"))
    )
    (net (code "133") (name "unconnected-(U$1-PF11-Pad133)") (class "Default")
      (node (ref "U$1") (pin "133") (pinfunction "PF11_133") (pintype "bidirectional"))
    )
    (net (code "134") (name "unconnected-(U$1-PF12-Pad132)") (class "Default")
      (node (ref "U$1") (pin "132") (pinfunction "PF12_132") (pintype "bidirectional"))
    )
    (net (code "135") (name "unconnected-(U$1-PF13-Pad130)") (class "Default")
      (node (ref "U$1") (pin "130") (pinfunction "PF13_130") (pintype "bidirectional"))
    )
    (net (code "136") (name "unconnected-(U$1-PF14-Pad121)") (class "Default")
      (node (ref "U$1") (pin "121") (pinfunction "PF14_121") (pintype "bidirectional"))
    )
    (net (code "137") (name "unconnected-(U$1-PF15-Pad131)") (class "Default")
      (node (ref "U$1") (pin "131") (pinfunction "PF15_131") (pintype "bidirectional"))
    )
    (net (code "138") (name "unconnected-(U$1-PG0-Pad60)") (class "Default")
      (node (ref "U$1") (pin "60") (pinfunction "PG0_60") (pintype "bidirectional"))
    )
    (net (code "139") (name "unconnected-(U$1-PG1-Pad57)") (class "Default")
      (node (ref "U$1") (pin "57") (pinfunction "PG1_57") (pintype "bidirectional"))
    )
    (net (code "140") (name "unconnected-(U$1-PG2-Pad41)") (class "Default")
      (node (ref "U$1") (pin "41") (pinfunction "PG2_41") (pintype "bidirectional"))
    )
    (net (code "141") (name "unconnected-(U$1-PG3-Pad43)") (class "Default")
      (node (ref "U$1") (pin "43") (pinfunction "PG3_43") (pintype "bidirectional"))
    )
    (net (code "142") (name "unconnected-(U$1-PG4-Pad142)") (class "Default")
      (node (ref "U$1") (pin "142") (pinfunction "PG4_142") (pintype "bidirectional"))
    )
    (net (code "143") (name "unconnected-(U$1-PG5-Pad139)") (class "Default")
      (node (ref "U$1") (pin "139") (pinfunction "PG5_139") (pintype "bidirectional"))
    )
    (net (code "144") (name "unconnected-(U$1-PG6-Pad141)") (class "Default")
      (node (ref "U$1") (pin "141") (pinfunction "PG6_141") (pintype "bidirectional"))
    )
    (net (code "145") (name "unconnected-(U$1-PG7-Pad140)") (class "Default")
      (node (ref "U$1") (pin "140") (pinfunction "PG7_140") (pintype "bidirectional"))
    )
    (net (code "146") (name "unconnected-(U$1-PG8-Pad137)") (class "Default")
      (node (ref "U$1") (pin "137") (pinfunction "PG8_137") (pintype "bidirectional"))
    )
    (net (code "147") (name "unconnected-(U$1-PG9-Pad64)") (class "Default")
      (node (ref "U$1") (pin "64") (pinfunction "PG9_64") (pintype "bidirectional"))
    )
    (net (code "148") (name "unconnected-(U$1-PG10-Pad65)") (class "Default")
      (node (ref "U$1") (pin "65") (pinfunction "PG10_65") (pintype "bidirectional"))
    )
    (net (code "149") (name "unconnected-(U$1-PG12-Pad66)") (class "Default")
      (node (ref "U$1") (pin "66") (pinfunction "PG12_66") (pintype "bidirectional"))
    )
    (net (code "150") (name "unconnected-(U$1-PG15-Pad63)") (class "Default")
      (node (ref "U$1") (pin "63") (pinfunction "PG15_63") (pintype "bidirectional"))
    )
    (net (code "151") (name "unconnected-(U$1-PH0-Pad30)") (class "Default")
      (node (ref "U$1") (pin "30") (pinfunction "PH0_30") (pintype "bidirectional"))
    )
    (net (code "152") (name "unconnected-(U$1-PH1-Pad32)") (class "Default")
      (node (ref "U$1") (pin "32") (pinfunction "PH1_32") (pintype "bidirectional"))
    )
    (net (code "153") (name "unconnected-(U$1-RESET-Pad13)") (class "Default")
      (node (ref "U$1") (pin "13") (pinfunction "RESET_13") (pintype "bidirectional"))
    )
    (net (code "154") (name "unconnected-(U$1-U5V-Pad79)") (class "Default")
      (node (ref "U$1") (pin "79") (pinfunction "U5V_79") (pintype "bidirectional"))
    )
    (net (code "155") (name "unconnected-(U$1-VDD-Pad6)") (class "Default")
      (node (ref "U$1") (pin "6") (pinfunction "VDD_6") (pintype "bidirectional"))
    )
    (net (code "156") (name "unconnected-(U$1-VIN-Pad23)") (class "Default")
      (node (ref "U$1") (pin "23") (pinfunction "VIN_23") (pintype "bidirectional"))
    )
    (net (code "157") (name "unconnected-(VBAT-+-Pad+@1)") (class "Default")
      (node (ref "VBAT") (pin "+@1") (pinfunction "+_+@1") (pintype "passive"))
    )
    (net (code "158") (name "unconnected-(WIFI-ADC-Pad10)") (class "Default")
      (node (ref "WIFI") (pin "10") (pinfunction "ADC_10") (pintype "bidirectional"))
    )
    (net (code "159") (name "unconnected-(WIFI-GPIO4-Pad6)") (class "Default")
      (node (ref "WIFI") (pin "6") (pinfunction "GPIO4_6") (pintype "bidirectional"))
    )
    (net (code "160") (name "unconnected-(WIFI-GPIO5-Pad5)") (class "Default")
      (node (ref "WIFI") (pin "5") (pinfunction "GPIO5_5") (pintype "bidirectional"))
    )
    (net (code "161") (name "unconnected-(WIFI-GPIO16-Pad12)") (class "Default")
      (node (ref "WIFI") (pin "12") (pinfunction "GPIO16_12") (pintype "bidirectional"))
    )
  )
)
